# gas-sensor.net
KiCad netlist of a schematic drawn in EAGLE
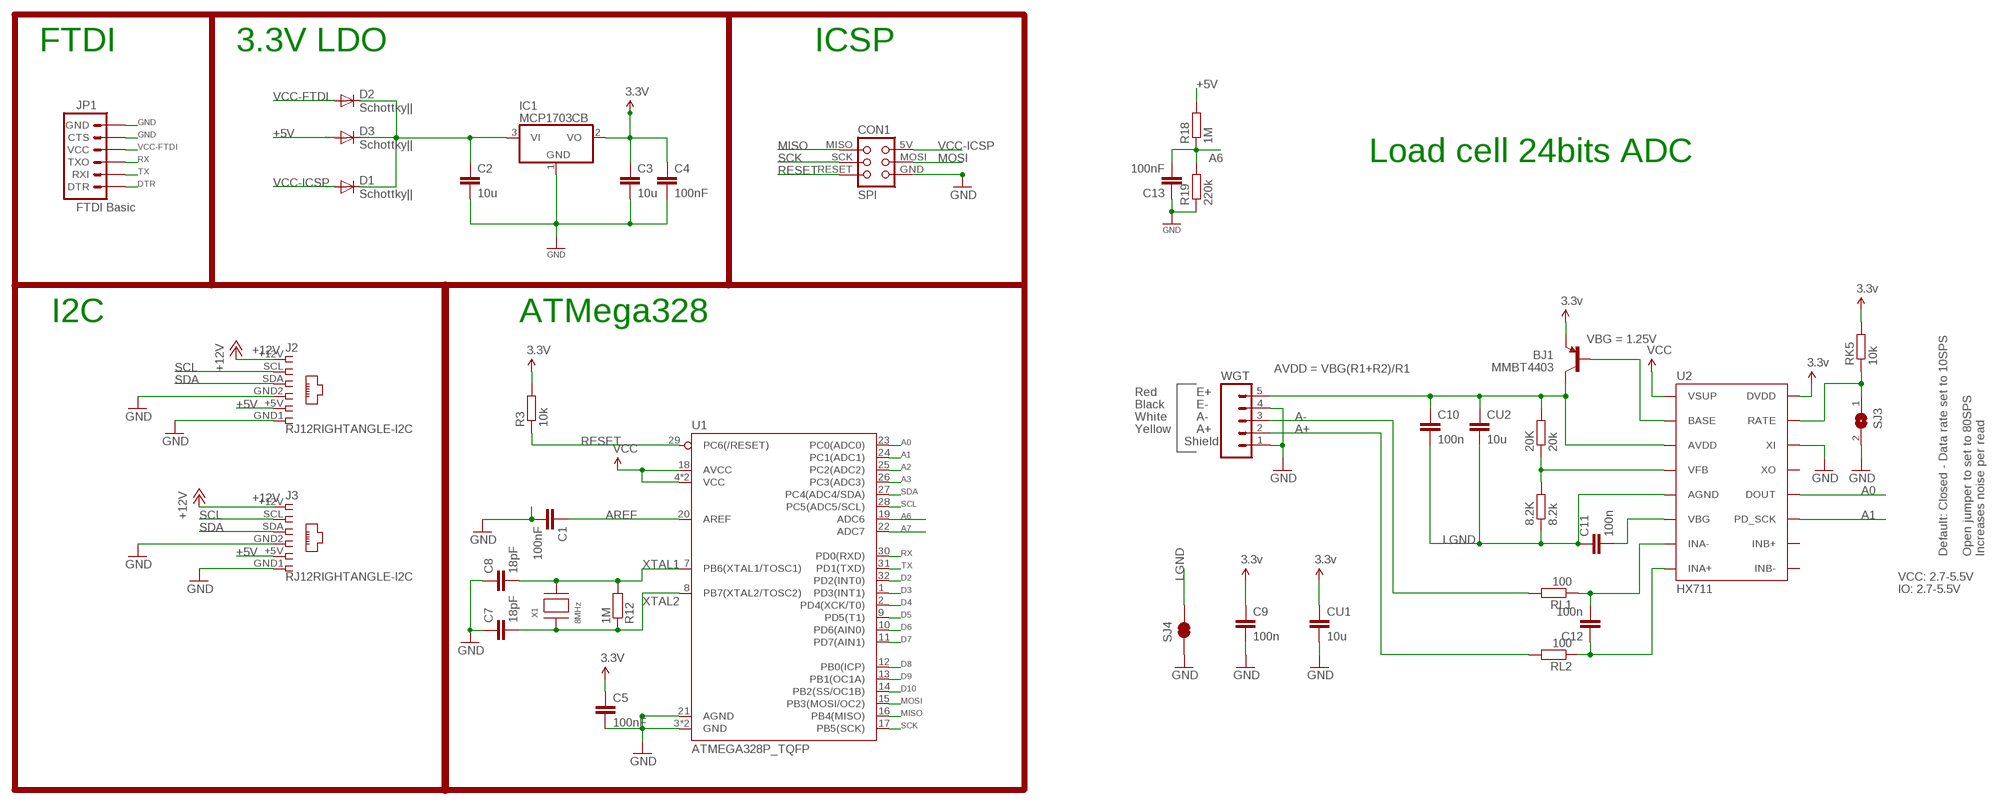
[diagram p0: schematic, sheet 1]

(export (version "E")
  (design (tool "Eeschema 10.0.6"))
  (components
    (comp (ref "8.2K")
      (value "8.2k")
      (footprint "eagle-import:M0805")
      (libsource (lib "eagle-import") (part "resistor_R-EU_M0805"))
    )
    (comp (ref "20K")
      (value "20k")
      (footprint "eagle-import:M0805")
      (libsource (lib "eagle-import") (part "resistor_R-EU_M0805"))
    )
    (comp (ref "BJ1")
      (value "MMBT4403")
      (footprint "eagle-import:SOT23-3")
      (libsource (lib "eagle-import") (part "TRANSISTOR_PNPMMBT4403"))
    )
    (comp (ref "C1")
      (value "100nF")
      (footprint "eagle-import:C0805K")
      (fields (field (name "MPN") "80-C1206C104K5R"))
      (libsource (lib "eagle-import") (part "rcl_334_C-EUC0805K"))
    )
    (comp (ref "C2")
      (value "10u")
      (footprint "eagle-import:C0805K")
      (fields (field (name "MPN") "77-VJ1206V106ZXQTBC"))
      (libsource (lib "eagle-import") (part "rcl_334_C-EUC0805K"))
    )
    (comp (ref "C3")
      (value "10u")
      (footprint "eagle-import:C0805K")
      (fields (field (name "MPN") "77-VJ1206V106ZXQTBC"))
      (libsource (lib "eagle-import") (part "rcl_334_C-EUC0805K"))
    )
    (comp (ref "C4")
      (value "100nF")
      (footprint "eagle-import:C0805K")
      (fields (field (name "MPN") "80-C1206C104K5R"))
      (libsource (lib "eagle-import") (part "rcl_334_C-EUC0805K"))
    )
    (comp (ref "C5")
      (value "100nF")
      (footprint "eagle-import:C0805K")
      (fields (field (name "MPN") "80-C1206C104K5R"))
      (libsource (lib "eagle-import") (part "rcl_334_C-EUC0805K"))
    )
    (comp (ref "C7")
      (value "18pF")
      (footprint "eagle-import:C0805K")
      (fields (field (name "MPN") "77-VJ1206A180JXXPBC"))
      (libsource (lib "eagle-import") (part "rcl_334_C-EUC0805K"))
    )
    (comp (ref "C8")
      (value "18pF")
      (footprint "eagle-import:C0805K")
      (fields (field (name "MPN") "77-VJ1206A180JXXPBC"))
      (libsource (lib "eagle-import") (part "rcl_334_C-EUC0805K"))
    )
    (comp (ref "C9")
      (value "100n")
      (footprint "eagle-import:C0805")
      (libsource (lib "eagle-import") (part "C-EUC0805"))
    )
    (comp (ref "C10")
      (value "100n")
      (footprint "eagle-import:C0805")
      (libsource (lib "eagle-import") (part "C-EUC0805"))
    )
    (comp (ref "C11")
      (value "100n")
      (footprint "eagle-import:C0805")
      (libsource (lib "eagle-import") (part "C-EUC0805"))
    )
    (comp (ref "C12")
      (value "100n")
      (footprint "eagle-import:C0805")
      (libsource (lib "eagle-import") (part "C-EUC0805"))
    )
    (comp (ref "C13")
      (value "100nF")
      (footprint "eagle-import:C0805K")
      (fields (field (name "MPN") "80-C1206C104K5R"))
      (libsource (lib "eagle-import") (part "rcl_334_C-EUC0805K"))
    )
    (comp (ref "CON1")
      (value "SPI")
      (footprint "eagle-import:TC2030-MCP")
      (libsource (lib "eagle-import") (part "TINYISPTAG"))
    )
    (comp (ref "CU1")
      (value "10u")
      (footprint "eagle-import:C0805")
      (libsource (lib "eagle-import") (part "C-EUC0805"))
    )
    (comp (ref "CU2")
      (value "10u")
      (footprint "eagle-import:C0805")
      (libsource (lib "eagle-import") (part "C-EUC0805"))
    )
    (comp (ref "D1")
      (value "Schottky||")
      (footprint "eagle-import:SOD123")
      (fields (field (name "MPN") "621-1N5819HW-F"))
      (libsource (lib "eagle-import") (part "MBR0520LT"))
    )
    (comp (ref "D2")
      (value "Schottky||")
      (footprint "eagle-import:SOD123")
      (fields (field (name "MPN") "621-1N5819HW-F"))
      (libsource (lib "eagle-import") (part "MBR0520LT"))
    )
    (comp (ref "D3")
      (value "Schottky||")
      (footprint "eagle-import:SOD123")
      (fields (field (name "MPN") "621-1N5819HW-F"))
      (libsource (lib "eagle-import") (part "MBR0520LT"))
    )
    (comp (ref "IC1")
      (value "MCP1703CB")
      (footprint "eagle-import:SOT23")
      (libsource (lib "eagle-import") (part "MCP1703CB"))
    )
    (comp (ref "J2")
      (value "RJ12RIGHTANGLE-I2C")
      (footprint "eagle-import:RJ12-RIGHTANGLE-I2C")
      (libsource (lib "eagle-import") (part "RJ12RIGHTANGLE-I2C"))
    )
    (comp (ref "J3")
      (value "RJ12RIGHTANGLE-I2C")
      (footprint "eagle-import:RJ12-RIGHTANGLE-I2C")
      (libsource (lib "eagle-import") (part "RJ12RIGHTANGLE-I2C"))
    )
    (comp (ref "JP1")
      (value "FTDI Basic")
      (footprint "eagle-import:1X06")
      (libsource (lib "eagle-import") (part "ARDUINO_SERIAL_PROGRAMPTH"))
    )
    (comp (ref "R3")
      (value "10k")
      (footprint "eagle-import:R0805")
      (libsource (lib "eagle-import") (part "R-EU_R0805"))
    )
    (comp (ref "R12")
      (value "1M")
      (footprint "eagle-import:R0805")
      (libsource (lib "eagle-import") (part "R-EU_R0805"))
    )
    (comp (ref "R18")
      (value "1M")
      (footprint "eagle-import:R0805")
      (libsource (lib "eagle-import") (part "R-EU_R0805"))
    )
    (comp (ref "R19")
      (value "220k")
      (footprint "eagle-import:R0805")
      (libsource (lib "eagle-import") (part "R-EU_R0805"))
    )
    (comp (ref "RK5")
      (value "10k")
      (footprint "eagle-import:M0805")
      (libsource (lib "eagle-import") (part "resistor_R-EU_M0805"))
    )
    (comp (ref "RL1")
      (value "100")
      (footprint "eagle-import:M0805")
      (libsource (lib "eagle-import") (part "resistor_R-EU_M0805"))
    )
    (comp (ref "RL2")
      (value "100")
      (footprint "eagle-import:M0805")
      (libsource (lib "eagle-import") (part "resistor_R-EU_M0805"))
    )
    (comp (ref "SJ3") (value "SJ") (footprint "eagle-import:SJ") (libsource (lib "eagle-import") (part "SJ")))
    (comp (ref "SJ4")
      (value "JUMPER-PAD-2-NC_BY_TRACE")
      (footprint "eagle-import:PAD-JUMPER-2-NC_BY_TRACE_YES_SILK")
      (libsource (lib "eagle-import") (part "JUMPER-PAD-2-NC_BY_TRACE"))
    )
    (comp (ref "U1")
      (value "ATMEGA328P_TQFP")
      (footprint "eagle-import:TQFP32-08")
      (libsource (lib "eagle-import") (part "ATMEGA328P_TQFP"))
    )
    (comp (ref "U2")
      (value "HX711")
      (footprint "eagle-import:SO16")
      (libsource (lib "eagle-import") (part "HX711HX711"))
    )
    (comp (ref "WGT")
      (value "M05PTH")
      (footprint "eagle-import:1X05")
      (libsource (lib "eagle-import") (part "M05PTH"))
    )
    (comp (ref "X1")
      (value "8MHz")
      (footprint "eagle-import:NX6035")
      (fields (field (name "MPN") "729-F60800010"))
      (libsource (lib "eagle-import") (part "XTALNX6035"))
    )
  )
  (nets
    (net (code "1") (name "+12V") (class "Default")
      (node (ref "J2") (pin "+12V") (pinfunction "1_+12V") (pintype "bidirectional"))
      (node (ref "J3") (pin "+12V") (pinfunction "1_+12V") (pintype "bidirectional"))
    )
    (net (code "2") (name "/+5V") (class "Default")
      (node (ref "D3") (pin "A") (pinfunction "A_A") (pintype "passive"))
      (node (ref "J2") (pin "+5V") (pinfunction "5_+5V") (pintype "bidirectional"))
      (node (ref "J3") (pin "+5V") (pinfunction "5_+5V") (pintype "bidirectional"))
      (node (ref "R18") (pin "2") (pinfunction "2_2") (pintype "passive"))
    )
    (net (code "3") (name "/A+") (class "Default")
      (node (ref "RL2") (pin "2") (pinfunction "2_2") (pintype "passive"))
      (node (ref "WGT") (pin "2") (pinfunction "2_2") (pintype "passive"))
    )
    (net (code "4") (name "/A-") (class "Default")
      (node (ref "RL1") (pin "2") (pinfunction "2_2") (pintype "passive"))
      (node (ref "WGT") (pin "3") (pinfunction "3_3") (pintype "passive"))
    )
    (net (code "5") (name "/A0") (class "Default")
      (node (ref "U1") (pin "23") (pinfunction "PC0(ADC0)_23") (pintype "bidirectional"))
      (node (ref "U2") (pin "12") (pinfunction "DOUT_12") (pintype "bidirectional"))
    )
    (net (code "6") (name "/A1") (class "Default")
      (node (ref "U1") (pin "24") (pinfunction "PC1(ADC1)_24") (pintype "bidirectional"))
      (node (ref "U2") (pin "11") (pinfunction "PD_SCK_11") (pintype "bidirectional"))
    )
    (net (code "7") (name "/A2") (class "Default")
      (node (ref "U1") (pin "25") (pinfunction "PC2(ADC2)_25") (pintype "bidirectional"))
    )
    (net (code "8") (name "/A3") (class "Default")
      (node (ref "U1") (pin "26") (pinfunction "PC3(ADC3)_26") (pintype "bidirectional"))
    )
    (net (code "9") (name "/A6") (class "Default")
      (node (ref "C13") (pin "2") (pinfunction "2_2") (pintype "passive"))
      (node (ref "R18") (pin "1") (pinfunction "1_1") (pintype "passive"))
      (node (ref "R19") (pin "2") (pinfunction "2_2") (pintype "passive"))
      (node (ref "U1") (pin "19") (pinfunction "ADC6_19") (pintype "bidirectional"))
    )
    (net (code "10") (name "/A7") (class "Default")
      (node (ref "U1") (pin "22") (pinfunction "ADC7_22") (pintype "bidirectional"))
    )
    (net (code "11") (name "/AREF") (class "Default")
      (node (ref "C1") (pin "1") (pinfunction "1_1") (pintype "passive"))
      (node (ref "U1") (pin "20") (pinfunction "AREF_20") (pintype "bidirectional"))
    )
    (net (code "12") (name "/D2") (class "Default")
      (node (ref "U1") (pin "32") (pinfunction "PD2(INT0)_32") (pintype "bidirectional"))
    )
    (net (code "13") (name "/D3") (class "Default")
      (node (ref "U1") (pin "1") (pinfunction "PD3(INT1)_1") (pintype "bidirectional"))
    )
    (net (code "14") (name "/D4") (class "Default")
      (node (ref "U1") (pin "2") (pinfunction "PD4(XCK/T0)_2") (pintype "bidirectional"))
    )
    (net (code "15") (name "/D5") (class "Default")
      (node (ref "U1") (pin "9") (pinfunction "PD5(T1)_9") (pintype "bidirectional"))
    )
    (net (code "16") (name "/D6") (class "Default")
      (node (ref "U1") (pin "10") (pinfunction "PD6(AIN0)_10") (pintype "bidirectional"))
    )
    (net (code "17") (name "/D7") (class "Default")
      (node (ref "U1") (pin "11") (pinfunction "PD7(AIN1)_11") (pintype "bidirectional"))
    )
    (net (code "18") (name "/D8") (class "Default")
      (node (ref "U1") (pin "12") (pinfunction "PB0(ICP)_12") (pintype "bidirectional"))
    )
    (net (code "19") (name "/D9") (class "Default")
      (node (ref "U1") (pin "13") (pinfunction "PB1(OC1A)_13") (pintype "bidirectional"))
    )
    (net (code "20") (name "/D10") (class "Default")
      (node (ref "U1") (pin "14") (pinfunction "PB2(SS/OC1B)_14") (pintype "bidirectional"))
    )
    (net (code "21") (name "/DTR") (class "Default")
      (node (ref "JP1") (pin "1") (pinfunction "DTR_1") (pintype "passive"))
    )
    (net (code "22") (name "/LGND") (class "Default")
      (node (ref "8.2K") (pin "1") (pinfunction "1_1") (pintype "passive"))
      (node (ref "C10") (pin "2") (pinfunction "2_2") (pintype "passive"))
      (node (ref "C11") (pin "1") (pinfunction "1_1") (pintype "passive"))
      (node (ref "CU2") (pin "2") (pinfunction "2_2") (pintype "passive"))
      (node (ref "SJ4") (pin "2") (pinfunction "2_2") (pintype "passive"))
      (node (ref "U2") (pin "5") (pinfunction "AGND_5") (pintype "bidirectional"))
    )
    (net (code "23") (name "/MISO") (class "Default")
      (node (ref "CON1") (pin "MISO") (pinfunction "MISO_MISO") (pintype "passive"))
      (node (ref "U1") (pin "16") (pinfunction "PB4(MISO)_16") (pintype "bidirectional"))
    )
    (net (code "24") (name "/MOSI") (class "Default")
      (node (ref "CON1") (pin "MOSI") (pinfunction "MOSI_MOSI") (pintype "passive"))
      (node (ref "U1") (pin "15") (pinfunction "PB3(MOSI/OC2)_15") (pintype "bidirectional"))
    )
    (net (code "25") (name "/RESET") (class "Default")
      (node (ref "CON1") (pin "RESET") (pinfunction "RESET_RESET") (pintype "passive"))
      (node (ref "R3") (pin "1") (pinfunction "1_1") (pintype "passive"))
      (node (ref "U1") (pin "29") (pinfunction "PC6(/RESET)_29") (pintype "bidirectional"))
    )
    (net (code "26") (name "/RX") (class "Default")
      (node (ref "JP1") (pin "3") (pinfunction "TXO_3") (pintype "passive"))
      (node (ref "U1") (pin "30") (pinfunction "PD0(RXD)_30") (pintype "bidirectional"))
    )
    (net (code "27") (name "/SCK") (class "Default")
      (node (ref "CON1") (pin "SCK") (pinfunction "SCK_SCK") (pintype "passive"))
      (node (ref "U1") (pin "17") (pinfunction "PB5(SCK)_17") (pintype "bidirectional"))
    )
    (net (code "28") (name "/SCL") (class "Default")
      (node (ref "J2") (pin "SCL") (pinfunction "2_SCL") (pintype "bidirectional"))
      (node (ref "J3") (pin "SCL") (pinfunction "2_SCL") (pintype "bidirectional"))
      (node (ref "U1") (pin "28") (pinfunction "PC5(ADC5/SCL)_28") (pintype "bidirectional"))
    )
    (net (code "29") (name "/SDA") (class "Default")
      (node (ref "J2") (pin "SDA") (pinfunction "3_SDA") (pintype "bidirectional"))
      (node (ref "J3") (pin "SDA") (pinfunction "3_SDA") (pintype "bidirectional"))
      (node (ref "U1") (pin "27") (pinfunction "PC4(ADC4/SDA)_27") (pintype "bidirectional"))
    )
    (net (code "30") (name "/TX") (class "Default")
      (node (ref "JP1") (pin "2") (pinfunction "RXI_2") (pintype "passive"))
      (node (ref "U1") (pin "31") (pinfunction "PD1(TXD)_31") (pintype "bidirectional"))
    )
    (net (code "31") (name "/VCC-FTDI") (class "Default")
      (node (ref "D2") (pin "A") (pinfunction "A_A") (pintype "passive"))
      (node (ref "JP1") (pin "4") (pinfunction "VCC_4") (pintype "passive"))
    )
    (net (code "32") (name "/VCC-ICSP") (class "Default")
      (node (ref "CON1") (pin "5V") (pinfunction "VCC_5V") (pintype "passive"))
      (node (ref "D1") (pin "A") (pinfunction "A_A") (pintype "passive"))
    )
    (net (code "33") (name "/XTAL1") (class "Default")
      (node (ref "C8") (pin "2") (pinfunction "2_2") (pintype "passive"))
      (node (ref "R12") (pin "2") (pinfunction "2_2") (pintype "passive"))
      (node (ref "U1") (pin "7") (pinfunction "PB6(XTAL1/TOSC1)_7") (pintype "bidirectional"))
      (node (ref "X1") (pin "P$2") (pinfunction "P$2_P$2") (pintype "bidirectional"))
    )
    (net (code "34") (name "/XTAL2") (class "Default")
      (node (ref "C7") (pin "2") (pinfunction "2_2") (pintype "passive"))
      (node (ref "R12") (pin "1") (pinfunction "1_1") (pintype "passive"))
      (node (ref "U1") (pin "8") (pinfunction "PB7(XTAL2/TOSC2)_8") (pintype "bidirectional"))
      (node (ref "X1") (pin "P$1") (pinfunction "P$1_P$1") (pintype "bidirectional"))
    )
    (net (code "35") (name "3.3V") (class "Default")
      (node (ref "BJ1") (pin "2") (pinfunction "E_2") (pintype "passive"))
      (node (ref "C3") (pin "1") (pinfunction "1_1") (pintype "passive"))
      (node (ref "C4") (pin "1") (pinfunction "1_1") (pintype "passive"))
      (node (ref "C5") (pin "1") (pinfunction "1_1") (pintype "passive"))
      (node (ref "C9") (pin "1") (pinfunction "1_1") (pintype "passive"))
      (node (ref "CU1") (pin "1") (pinfunction "1_1") (pintype "passive"))
      (node (ref "IC1") (pin "2") (pinfunction "VO_2") (pintype "passive"))
      (node (ref "R3") (pin "2") (pinfunction "2_2") (pintype "passive"))
      (node (ref "RK5") (pin "2") (pinfunction "2_2") (pintype "passive"))
      (node (ref "U1") (pin "18") (pinfunction "AVCC_18") (pintype "bidirectional"))
      (node (ref "U1") (pin "4") (pinfunction "VCC_4") (pintype "bidirectional"))
      (node (ref "U1") (pin "6") (pinfunction "VCC_6") (pintype "bidirectional"))
      (node (ref "U2") (pin "1") (pinfunction "VSUP_1") (pintype "bidirectional"))
      (node (ref "U2") (pin "16") (pinfunction "DVDD_16") (pintype "bidirectional"))
    )
    (net (code "36") (name "GND") (class "Default")
      (node (ref "C1") (pin "2") (pinfunction "2_2") (pintype "passive"))
      (node (ref "C13") (pin "1") (pinfunction "1_1") (pintype "passive"))
      (node (ref "C2") (pin "2") (pinfunction "2_2") (pintype "passive"))
      (node (ref "C3") (pin "2") (pinfunction "2_2") (pintype "passive"))
      (node (ref "C4") (pin "2") (pinfunction "2_2") (pintype "passive"))
      (node (ref "C5") (pin "2") (pinfunction "2_2") (pintype "passive"))
      (node (ref "C7") (pin "1") (pinfunction "1_1") (pintype "passive"))
      (node (ref "C8") (pin "1") (pinfunction "1_1") (pintype "passive"))
      (node (ref "C9") (pin "2") (pinfunction "2_2") (pintype "passive"))
      (node (ref "CON1") (pin "GND") (pinfunction "GND_GND") (pintype "passive"))
      (node (ref "CU1") (pin "2") (pinfunction "2_2") (pintype "passive"))
      (node (ref "IC1") (pin "1") (pinfunction "GND_1") (pintype "passive"))
      (node (ref "J2") (pin "GND1") (pinfunction "6_GND1") (pintype "bidirectional"))
      (node (ref "J2") (pin "GND2") (pinfunction "4_GND2") (pintype "bidirectional"))
      (node (ref "J3") (pin "GND1") (pinfunction "6_GND1") (pintype "bidirectional"))
      (node (ref "J3") (pin "GND2") (pinfunction "4_GND2") (pintype "bidirectional"))
      (node (ref "JP1") (pin "5") (pinfunction "CTS_5") (pintype "passive"))
      (node (ref "JP1") (pin "6") (pinfunction "GND_6") (pintype "passive"))
      (node (ref "R19") (pin "1") (pinfunction "1_1") (pintype "passive"))
      (node (ref "SJ3") (pin "2") (pinfunction "2_2") (pintype "passive"))
      (node (ref "SJ4") (pin "1") (pinfunction "1_1") (pintype "passive"))
      (node (ref "U1") (pin "21") (pinfunction "AGND_21") (pintype "bidirectional"))
      (node (ref "U1") (pin "3") (pinfunction "GND_3") (pintype "bidirectional"))
      (node (ref "U1") (pin "5") (pinfunction "GND_5") (pintype "bidirectional"))
      (node (ref "U2") (pin "14") (pinfunction "XI_14") (pintype "bidirectional"))
      (node (ref "WGT") (pin "1") (pinfunction "1_1") (pintype "passive"))
      (node (ref "WGT") (pin "4") (pinfunction "4_4") (pintype "passive"))
    )
    (net (code "37") (name "Net-(BJ1-B)") (class "Default")
      (node (ref "BJ1") (pin "1") (pinfunction "B_1") (pintype "passive"))
      (node (ref "U2") (pin "2") (pinfunction "BASE_2") (pintype "bidirectional"))
    )
    (net (code "38") (name "Net-(BJ1-C)") (class "Default")
      (node (ref "20K") (pin "2") (pinfunction "2_2") (pintype "passive"))
      (node (ref "BJ1") (pin "3") (pinfunction "C_3") (pintype "passive"))
      (node (ref "C10") (pin "1") (pinfunction "1_1") (pintype "passive"))
      (node (ref "CU2") (pin "1") (pinfunction "1_1") (pintype "passive"))
      (node (ref "U2") (pin "3") (pinfunction "AVDD_3") (pintype "bidirectional"))
      (node (ref "WGT") (pin "5") (pinfunction "5_5") (pintype "passive"))
    )
    (net (code "39") (name "Net-(IC1-VI)") (class "Default")
      (node (ref "C2") (pin "1") (pinfunction "1_1") (pintype "passive"))
      (node (ref "D1") (pin "C") (pinfunction "C_C") (pintype "passive"))
      (node (ref "D2") (pin "C") (pinfunction "C_C") (pintype "passive"))
      (node (ref "D3") (pin "C") (pinfunction "C_C") (pintype "passive"))
      (node (ref "IC1") (pin "3") (pinfunction "VI_3") (pintype "input"))
    )
    (net (code "40") (name "Net-(U2-INA+)") (class "Default")
      (node (ref "C12") (pin "1") (pinfunction "1_1") (pintype "passive"))
      (node (ref "RL2") (pin "1") (pinfunction "1_1") (pintype "passive"))
      (node (ref "U2") (pin "8") (pinfunction "INA+_8") (pintype "bidirectional"))
    )
    (net (code "41") (name "Net-(U2-INA-)") (class "Default")
      (node (ref "C12") (pin "2") (pinfunction "2_2") (pintype "passive"))
      (node (ref "RL1") (pin "1") (pinfunction "1_1") (pintype "passive"))
      (node (ref "U2") (pin "7") (pinfunction "INA-_7") (pintype "bidirectional"))
    )
    (net (code "42") (name "Net-(U2-RATE)") (class "Default")
      (node (ref "RK5") (pin "1") (pinfunction "1_1") (pintype "passive"))
      (node (ref "SJ3") (pin "1") (pinfunction "1_1") (pintype "passive"))
      (node (ref "U2") (pin "15") (pinfunction "RATE_15") (pintype "bidirectional"))
    )
    (net (code "43") (name "Net-(U2-VBG)") (class "Default")
      (node (ref "C11") (pin "2") (pinfunction "2_2") (pintype "passive"))
      (node (ref "U2") (pin "6") (pinfunction "VBG_6") (pintype "bidirectional"))
    )
    (net (code "44") (name "Net-(U2-VFB)") (class "Default")
      (node (ref "20K") (pin "1") (pinfunction "1_1") (pintype "passive"))
      (node (ref "8.2K") (pin "2") (pinfunction "2_2") (pintype "passive"))
      (node (ref "U2") (pin "4") (pinfunction "VFB_4") (pintype "bidirectional"))
    )
    (net (code "45") (name "unconnected-(U2-INB+-Pad10)") (class "Default")
      (node (ref "U2") (pin "10") (pinfunction "INB+_10") (pintype "bidirectional"))
    )
    (net (code "46") (name "unconnected-(U2-INB--Pad9)") (class "Default")
      (node (ref "U2") (pin "9") (pinfunction "INB-_9") (pintype "bidirectional"))
    )
    (net (code "47") (name "unconnected-(U2-XO-Pad13)") (class "Default")
      (node (ref "U2") (pin "13") (pinfunction "XO_13") (pintype "bidirectional"))
    )
  )
)
